# hss-mag-enc-v2.net
KiCad netlist of a schematic drawn in EAGLE
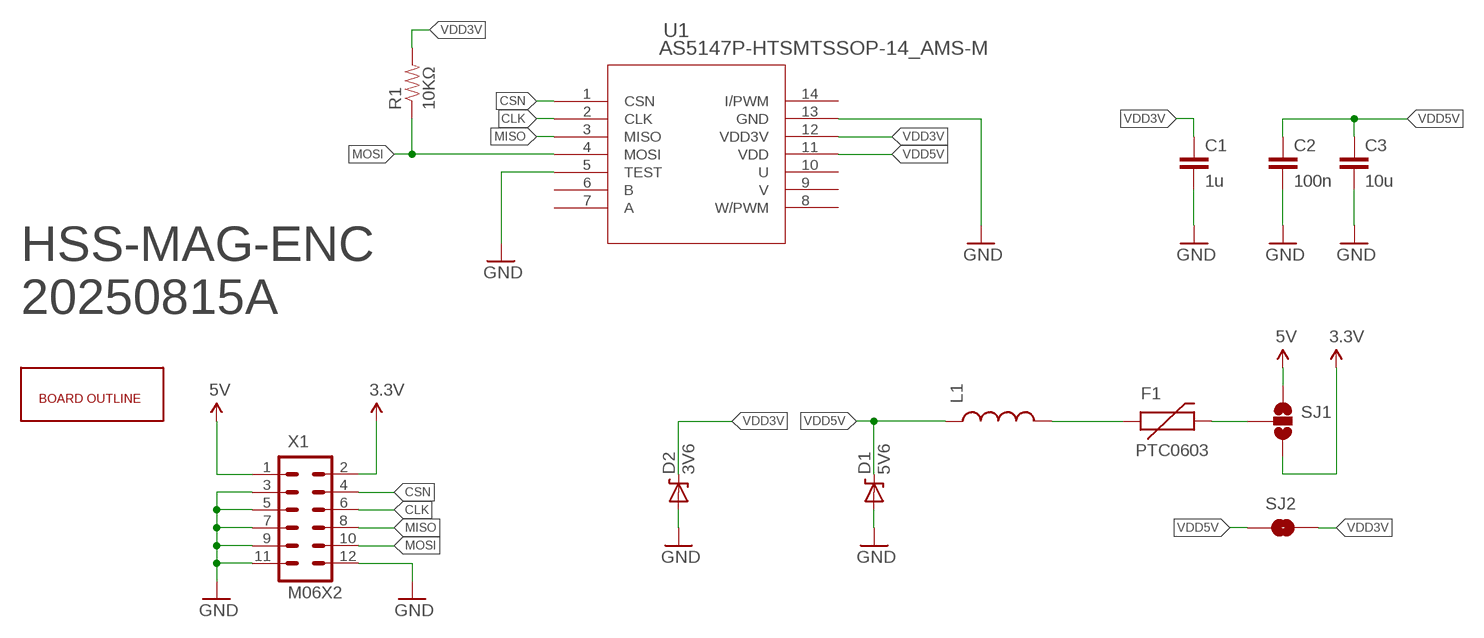
[diagram p0: schematic, sheet 1]

(export (version "E")
  (design (tool "Eeschema 10.0.6"))
  (components
    (comp (ref "C1")
      (value "1u")
      (footprint "eagle-import:0805")
      (libsource (lib "eagle-import") (part "CAP0805"))
    )
    (comp (ref "C2")
      (value "100n")
      (footprint "eagle-import:0805")
      (libsource (lib "eagle-import") (part "CAP0805"))
    )
    (comp (ref "C3")
      (value "10u")
      (footprint "eagle-import:0805")
      (libsource (lib "eagle-import") (part "CAP0805"))
    )
    (comp (ref "D1")
      (value "5V6")
      (footprint "eagle-import:SOD-323")
      (libsource (lib "eagle-import") (part "DIODE-ZENER-BZT52"))
    )
    (comp (ref "D2")
      (value "3V6")
      (footprint "eagle-import:SOD-323")
      (libsource (lib "eagle-import") (part "DIODE-ZENER-BZT52"))
    )
    (comp (ref "F1")
      (value "PTC0603")
      (footprint "eagle-import:0603")
      (libsource (lib "eagle-import") (part "PTC0603"))
    )
    (comp (ref "L1")
      (value "INDUCTOR0805")
      (footprint "eagle-import:0805")
      (libsource (lib "eagle-import") (part "INDUCTOR0805"))
    )
    (comp (ref "R1")
      (value "10KΩ")
      (footprint "eagle-import:0603-RES")
      (libsource (lib "eagle-import") (part "RESISTOR0603-RES"))
    )
    (comp (ref "SJ1")
      (value "SOLDERJUMPER_2WAYS")
      (footprint "eagle-import:SJ_3")
      (libsource (lib "eagle-import") (part "SOLDERJUMPER_2WAYS"))
    )
    (comp (ref "SJ2")
      (value "SOLDERJUMPERNO")
      (footprint "eagle-import:SJ_2S-NO")
      (libsource (lib "eagle-import") (part "SOLDERJUMPERNO"))
    )
    (comp (ref "U$1")
      (value "BOARD-OUTLINE-V2")
      (footprint "eagle-import:BOARD-OUTLINE-2")
      (libsource (lib "eagle-import") (part "BOARD-OUTLINE-V2"))
    )
    (comp (ref "U1")
      (value "AS5147P-HTSMTSSOP-14_AMS-M")
      (footprint "eagle-import:TSSOP-14_AMS-M")
      (fields
        (field (name "MANUFACTURER_PART_NUMBER") "AS5147P-HTSM")
        (field (name "COPYRIGHT") "Copyright (C) 2025 Ultra Librarian. All rights reserved.")
      )
      (libsource (lib "eagle-import") (part "AS5147P-HTSMTSSOP-14_AMS-M"))
    )
    (comp (ref "X1")
      (value "M06X2")
      (footprint "eagle-import:2X6")
      (libsource (lib "eagle-import") (part "M06X2"))
    )
  )
  (nets
    (net (code "1") (name "3.3V") (class "Default")
      (node (ref "SJ1") (pin "3") (pinfunction "3_3") (pintype "passive"))
      (node (ref "X1") (pin "2") (pinfunction "2_2") (pintype "passive"))
    )
    (net (code "2") (name "5V") (class "Default")
      (node (ref "SJ1") (pin "1") (pinfunction "1_1") (pintype "passive"))
      (node (ref "X1") (pin "1") (pinfunction "1_1") (pintype "passive"))
    )
    (net (code "3") (name "CLK") (class "Default")
      (node (ref "U1") (pin "2") (pinfunction "CLK_2") (pintype "input"))
      (node (ref "X1") (pin "6") (pinfunction "6_6") (pintype "passive"))
    )
    (net (code "4") (name "CSN") (class "Default")
      (node (ref "U1") (pin "1") (pinfunction "CSN_1") (pintype "input"))
      (node (ref "X1") (pin "4") (pinfunction "4_4") (pintype "passive"))
    )
    (net (code "5") (name "GND") (class "Default")
      (node (ref "C1") (pin "2") (pinfunction "2_2") (pintype "passive"))
      (node (ref "C2") (pin "2") (pinfunction "2_2") (pintype "passive"))
      (node (ref "C3") (pin "2") (pinfunction "2_2") (pintype "passive"))
      (node (ref "D1") (pin "2") (pinfunction "A_2") (pintype "passive"))
      (node (ref "D2") (pin "2") (pinfunction "A_2") (pintype "passive"))
      (node (ref "U1") (pin "13") (pinfunction "GND_13") (pintype "passive"))
      (node (ref "U1") (pin "5") (pinfunction "TEST_5") (pintype "passive"))
      (node (ref "X1") (pin "11") (pinfunction "11_11") (pintype "passive"))
      (node (ref "X1") (pin "12") (pinfunction "12_12") (pintype "passive"))
      (node (ref "X1") (pin "3") (pinfunction "3_3") (pintype "passive"))
      (node (ref "X1") (pin "5") (pinfunction "5_5") (pintype "passive"))
      (node (ref "X1") (pin "7") (pinfunction "7_7") (pintype "passive"))
      (node (ref "X1") (pin "9") (pinfunction "9_9") (pintype "passive"))
    )
    (net (code "6") (name "MISO") (class "Default")
      (node (ref "U1") (pin "3") (pinfunction "MISO_3") (pintype "output"))
      (node (ref "X1") (pin "8") (pinfunction "8_8") (pintype "passive"))
    )
    (net (code "7") (name "MOSI") (class "Default")
      (node (ref "R1") (pin "1") (pinfunction "1_1") (pintype "passive"))
      (node (ref "U1") (pin "4") (pinfunction "MOSI_4") (pintype "input"))
      (node (ref "X1") (pin "10") (pinfunction "10_10") (pintype "passive"))
    )
    (net (code "8") (name "Net-(F1-Pad1)") (class "Default")
      (node (ref "F1") (pin "1") (pinfunction "1_1") (pintype "bidirectional"))
      (node (ref "L1") (pin "2") (pinfunction "2_2") (pintype "passive"))
    )
    (net (code "9") (name "Net-(F1-Pad2)") (class "Default")
      (node (ref "F1") (pin "2") (pinfunction "2_2") (pintype "bidirectional"))
      (node (ref "SJ1") (pin "2") (pinfunction "2_2") (pintype "passive"))
    )
    (net (code "10") (name "VDD3V") (class "Default")
      (node (ref "C1") (pin "1") (pinfunction "1_1") (pintype "passive"))
      (node (ref "D2") (pin "1") (pinfunction "C_1") (pintype "passive"))
      (node (ref "R1") (pin "2") (pinfunction "2_2") (pintype "passive"))
      (node (ref "SJ2") (pin "2") (pinfunction "2_2") (pintype "passive"))
      (node (ref "U1") (pin "12") (pinfunction "VDD3V_12") (pintype "power_in"))
    )
    (net (code "11") (name "VDD5V") (class "Default")
      (node (ref "C2") (pin "1") (pinfunction "1_1") (pintype "passive"))
      (node (ref "C3") (pin "1") (pinfunction "1_1") (pintype "passive"))
      (node (ref "D1") (pin "1") (pinfunction "C_1") (pintype "passive"))
      (node (ref "L1") (pin "1") (pinfunction "1_1") (pintype "passive"))
      (node (ref "SJ2") (pin "1") (pinfunction "1_1") (pintype "passive"))
      (node (ref "U1") (pin "11") (pinfunction "VDD_11") (pintype "power_in"))
    )
    (net (code "12") (name "unconnected-(U1-A-Pad7)") (class "Default")
      (node (ref "U1") (pin "7") (pinfunction "A_7") (pintype "output"))
    )
    (net (code "13") (name "unconnected-(U1-B-Pad6)") (class "Default")
      (node (ref "U1") (pin "6") (pinfunction "B_6") (pintype "output"))
    )
    (net (code "14") (name "unconnected-(U1-I{slash}PWM-Pad14)") (class "Default")
      (node (ref "U1") (pin "14") (pinfunction "I/PWM_14") (pintype "input"))
    )
    (net (code "15") (name "unconnected-(U1-U-Pad10)") (class "Default")
      (node (ref "U1") (pin "10") (pinfunction "U_10") (pintype "output"))
    )
    (net (code "16") (name "unconnected-(U1-V-Pad9)") (class "Default")
      (node (ref "U1") (pin "9") (pinfunction "V_9") (pintype "output"))
    )
    (net (code "17") (name "unconnected-(U1-W{slash}PWM-Pad8)") (class "Default")
      (node (ref "U1") (pin "8") (pinfunction "W/PWM_8") (pintype "output"))
    )
  )
)
